# CanarySchematic3_0.net
KiCad netlist of a schematic drawn in EAGLE
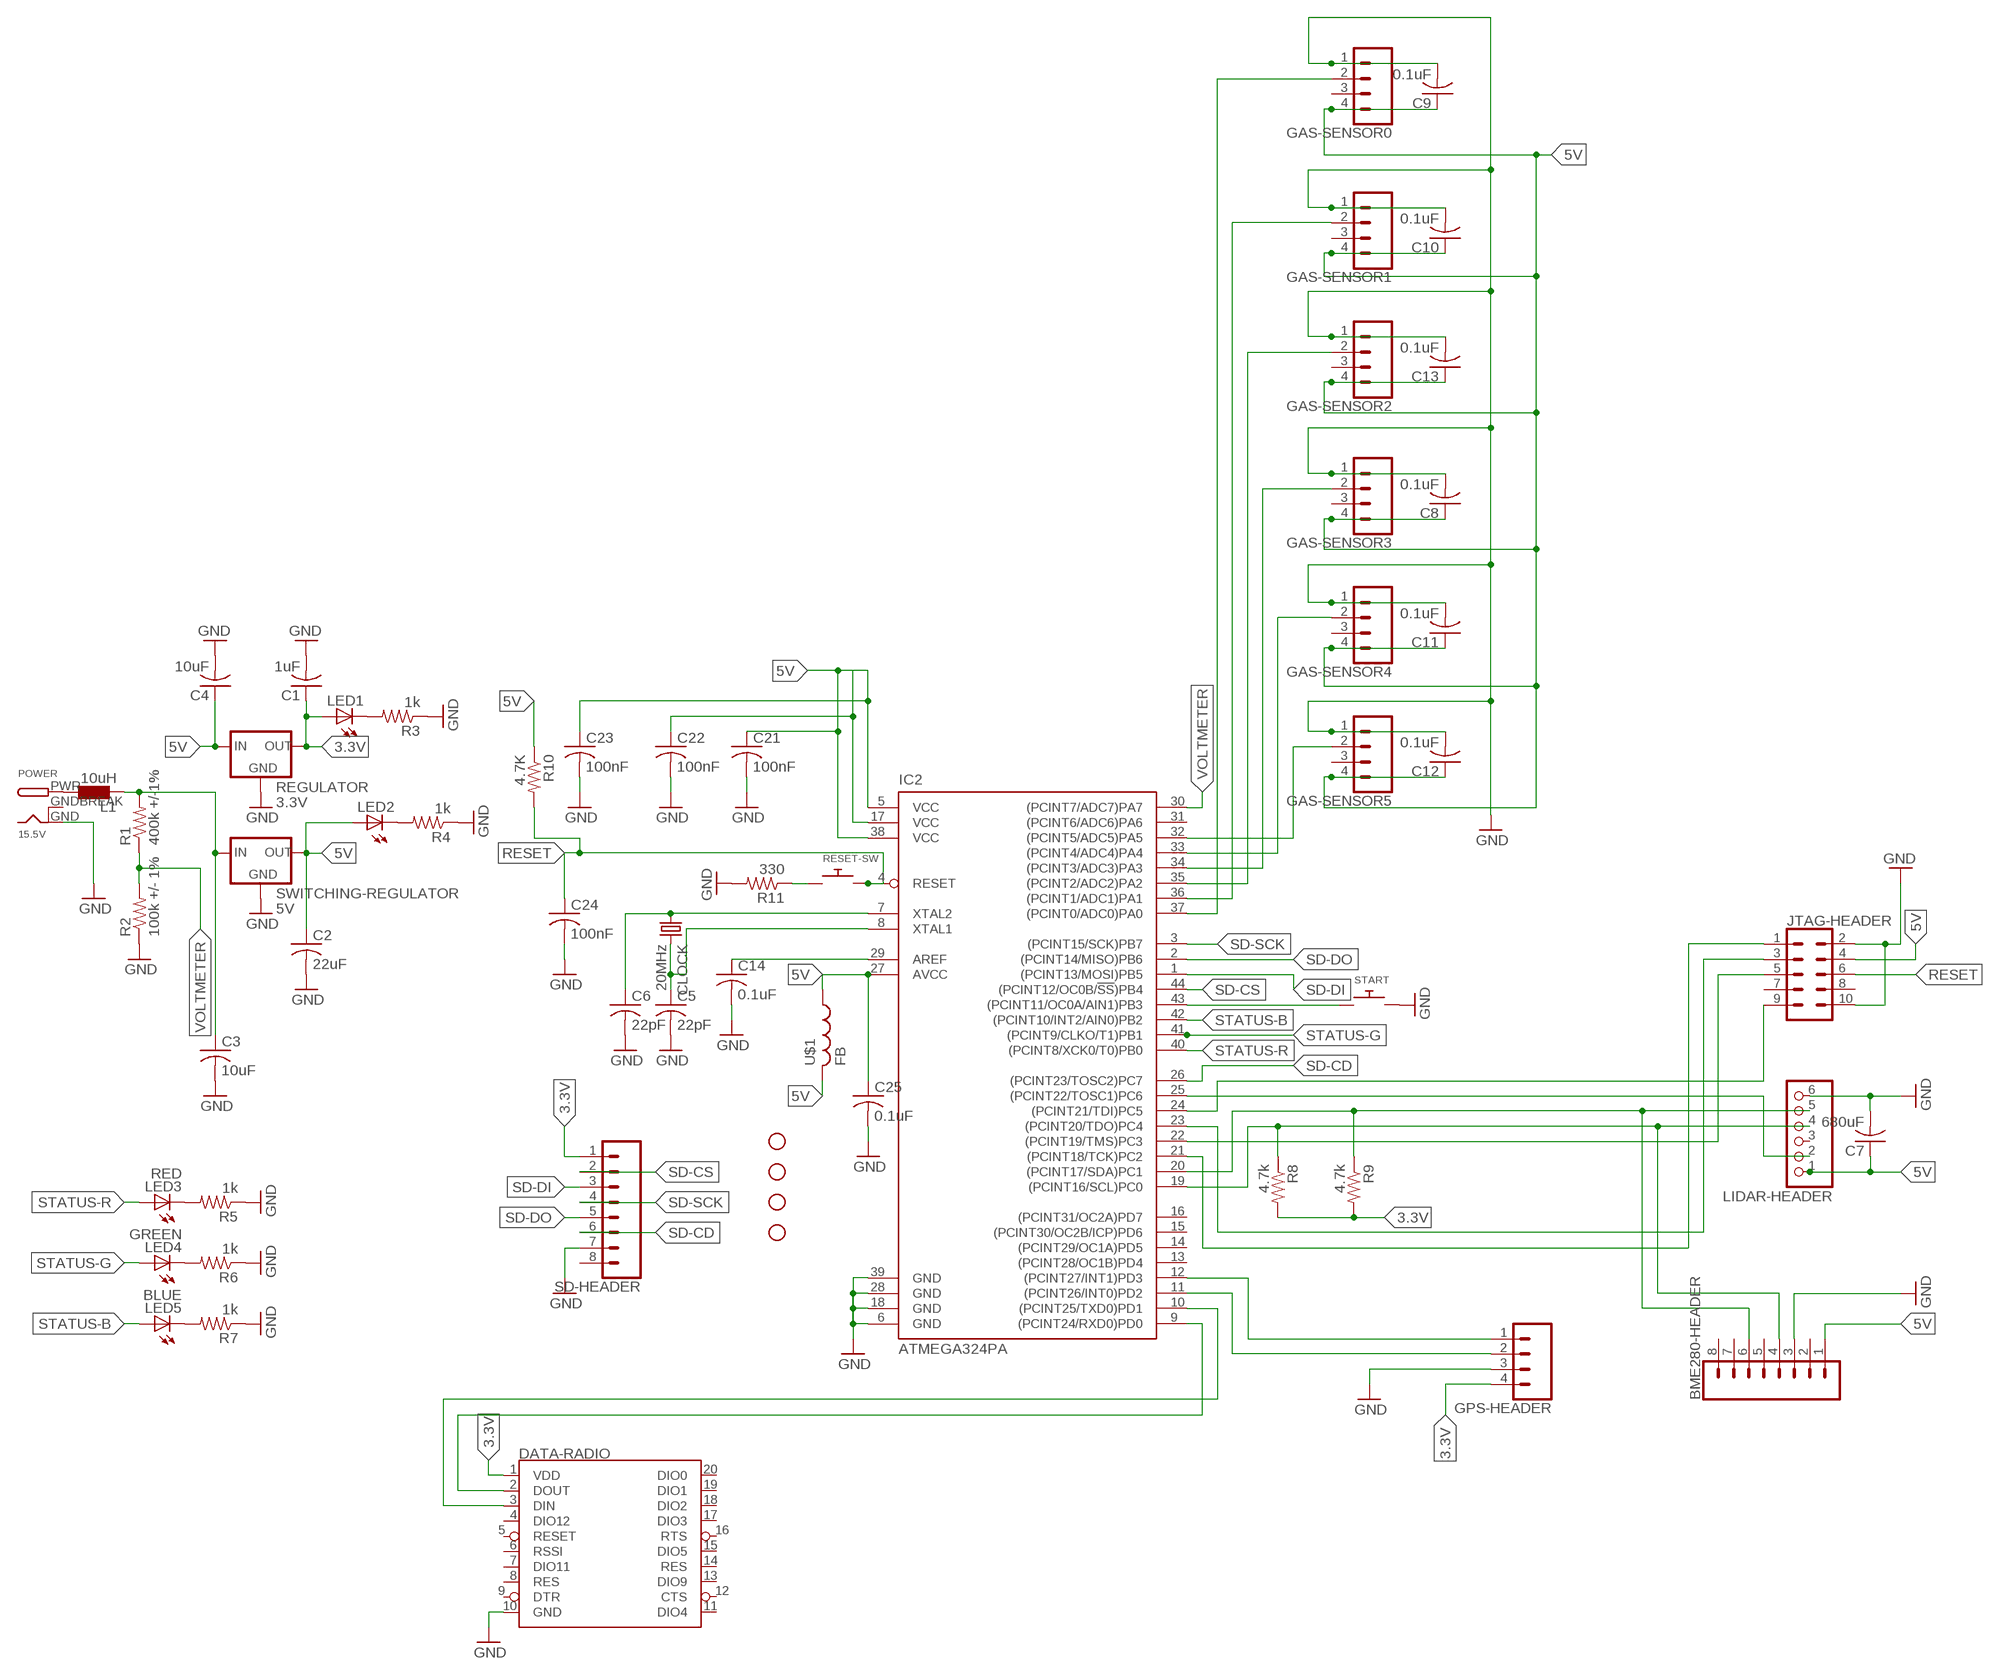
[diagram p0: schematic, sheet 1]

(export (version "E")
  (design (tool "Eeschema 10.0.6"))
  (components
    (comp (ref "BME280-HEADER")
      (value "CONN_08\"")
      (footprint "eagle-import:1X08")
      (libsource (lib "eagle-import") (part "CONN_08{dblquote}"))
    )
    (comp (ref "C1")
      (value "1uF")
      (footprint "eagle-import:C0805")
      (libsource (lib "eagle-import") (part "C-USC0805"))
    )
    (comp (ref "C2")
      (value "22uF")
      (footprint "eagle-import:C0805")
      (libsource (lib "eagle-import") (part "C-USC0805"))
    )
    (comp (ref "C3")
      (value "10uF")
      (footprint "eagle-import:C0805")
      (libsource (lib "eagle-import") (part "C-USC0805"))
    )
    (comp (ref "C4")
      (value "10uF")
      (footprint "eagle-import:C0805")
      (libsource (lib "eagle-import") (part "C-USC0805"))
    )
    (comp (ref "C5")
      (value "22pF")
      (footprint "eagle-import:C0805")
      (libsource (lib "eagle-import") (part "C-USC0805"))
    )
    (comp (ref "C6")
      (value "22pF")
      (footprint "eagle-import:C0805")
      (libsource (lib "eagle-import") (part "C-USC0805"))
    )
    (comp (ref "C7")
      (value "680uF")
      (footprint "eagle-import:C0805")
      (libsource (lib "eagle-import") (part "C-USC0805"))
    )
    (comp (ref "C8")
      (value "0.1uF")
      (footprint "eagle-import:C0805")
      (libsource (lib "eagle-import") (part "C-USC0805"))
    )
    (comp (ref "C9")
      (value "0.1uF")
      (footprint "eagle-import:C0805")
      (libsource (lib "eagle-import") (part "C-USC0805"))
    )
    (comp (ref "C10")
      (value "0.1uF")
      (footprint "eagle-import:C0805")
      (libsource (lib "eagle-import") (part "C-USC0805"))
    )
    (comp (ref "C11")
      (value "0.1uF")
      (footprint "eagle-import:C0805")
      (libsource (lib "eagle-import") (part "C-USC0805"))
    )
    (comp (ref "C12")
      (value "0.1uF")
      (footprint "eagle-import:C0603")
      (libsource (lib "eagle-import") (part "C-USC0603"))
    )
    (comp (ref "C13")
      (value "0.1uF")
      (footprint "eagle-import:C0805")
      (libsource (lib "eagle-import") (part "C-USC0805"))
    )
    (comp (ref "C14")
      (value "0.1uF")
      (footprint "eagle-import:C0805")
      (libsource (lib "eagle-import") (part "C-USC0805"))
    )
    (comp (ref "C21")
      (value "100nF")
      (footprint "eagle-import:C0805")
      (libsource (lib "eagle-import") (part "C-USC0805"))
    )
    (comp (ref "C22")
      (value "100nF")
      (footprint "eagle-import:C0805")
      (libsource (lib "eagle-import") (part "C-USC0805"))
    )
    (comp (ref "C23")
      (value "100nF")
      (footprint "eagle-import:C0805")
      (libsource (lib "eagle-import") (part "C-USC0805"))
    )
    (comp (ref "C24")
      (value "100nF")
      (footprint "eagle-import:C0805")
      (libsource (lib "eagle-import") (part "C-USC0805"))
    )
    (comp (ref "C25")
      (value "0.1uF")
      (footprint "eagle-import:C0805")
      (libsource (lib "eagle-import") (part "C-USC0805"))
    )
    (comp (ref "CLOCK")
      (value "20MHz")
      (footprint "eagle-import:86SMX")
      (libsource (lib "eagle-import") (part "CRYSTAL68SMX"))
    )
    (comp (ref "DATA-RADIO")
      (value "XBEE")
      (footprint "eagle-import:XBEE")
      (libsource (lib "eagle-import") (part "XBEE"))
    )
    (comp (ref "GAS-SENSOR0")
      (value "CONN_04")
      (footprint "eagle-import:1X04")
      (libsource (lib "eagle-import") (part "CONN_04"))
    )
    (comp (ref "GAS-SENSOR1")
      (value "CONN_04")
      (footprint "eagle-import:1X04")
      (libsource (lib "eagle-import") (part "CONN_04"))
    )
    (comp (ref "GAS-SENSOR2")
      (value "CONN_04")
      (footprint "eagle-import:1X04")
      (libsource (lib "eagle-import") (part "CONN_04"))
    )
    (comp (ref "GAS-SENSOR3")
      (value "CONN_04")
      (footprint "eagle-import:1X04")
      (libsource (lib "eagle-import") (part "CONN_04"))
    )
    (comp (ref "GAS-SENSOR4")
      (value "CONN_04")
      (footprint "eagle-import:1X04")
      (libsource (lib "eagle-import") (part "CONN_04"))
    )
    (comp (ref "GAS-SENSOR5")
      (value "CONN_04")
      (footprint "eagle-import:1X04")
      (libsource (lib "eagle-import") (part "CONN_04"))
    )
    (comp (ref "GPS-HEADER")
      (value "CONN_04")
      (footprint "eagle-import:1X04")
      (libsource (lib "eagle-import") (part "CONN_04"))
    )
    (comp (ref "H8")
      (value "STAND-OFF")
      (footprint "eagle-import:STAND-OFF")
      (libsource (lib "eagle-import") (part "STAND-OFF"))
    )
    (comp (ref "IC2")
      (value "ATMEGA324PA")
      (footprint "eagle-import:TQFP44")
      (fields (field (name "MPN") "ATMEGA644PV-10AU"))
      (libsource (lib "eagle-import") (part "ATMEGA644A"))
    )
    (comp (ref "JTAG-HEADER")
      (value "CONN_05X2PTH")
      (footprint "eagle-import:2X5")
      (libsource (lib "eagle-import") (part "CONN_05X2PTH"))
    )
    (comp (ref "L1")
      (value "10uH")
      (footprint "eagle-import:L1812")
      (libsource (lib "eagle-import") (part "L"))
    )
    (comp (ref "LED1")
      (value "LEDCHIP-LED0805")
      (footprint "eagle-import:CHIP-LED0805")
      (libsource (lib "eagle-import") (part "LEDCHIP-LED0805"))
    )
    (comp (ref "LED2")
      (value "LEDCHIP-LED0805")
      (footprint "eagle-import:CHIP-LED0805")
      (libsource (lib "eagle-import") (part "LEDCHIP-LED0805"))
    )
    (comp (ref "LED3")
      (value "RED")
      (footprint "eagle-import:CHIP-LED0805")
      (libsource (lib "eagle-import") (part "LEDCHIP-LED0805"))
    )
    (comp (ref "LED4")
      (value "GREEN")
      (footprint "eagle-import:CHIP-LED0805")
      (libsource (lib "eagle-import") (part "LEDCHIP-LED0805"))
    )
    (comp (ref "LED5")
      (value "BLUE")
      (footprint "eagle-import:CHIP-LED0805")
      (libsource (lib "eagle-import") (part "LEDCHIP-LED0805"))
    )
    (comp (ref "LIDAR-HEADER")
      (value "PINHD-1X6")
      (footprint "eagle-import:1X06")
      (libsource (lib "eagle-import") (part "PINHD-1X6"))
    )
    (comp (ref "MOUNT-HOLE1")
      (value "STAND-OFF")
      (footprint "eagle-import:STAND-OFF")
      (libsource (lib "eagle-import") (part "STAND-OFF"))
    )
    (comp (ref "MOUNT-HOLE2")
      (value "STAND-OFF")
      (footprint "eagle-import:STAND-OFF")
      (libsource (lib "eagle-import") (part "STAND-OFF"))
    )
    (comp (ref "MOUNT-HOLE3")
      (value "STAND-OFF")
      (footprint "eagle-import:STAND-OFF")
      (libsource (lib "eagle-import") (part "STAND-OFF"))
    )
    (comp (ref "POWER")
      (value "15.5V")
      (footprint "eagle-import:DCJACK_2MM_PTH")
      (libsource (lib "eagle-import") (part "DCBARRELPTH"))
    )
    (comp (ref "R1")
      (value "400k +/-1%")
      (footprint "eagle-import:M0805")
      (libsource (lib "eagle-import") (part "R-US_M0805"))
    )
    (comp (ref "R2")
      (value "100k +/- 1%")
      (footprint "eagle-import:M0805")
      (libsource (lib "eagle-import") (part "R-US_M0805"))
    )
    (comp (ref "R3")
      (value "1k")
      (footprint "eagle-import:M0805")
      (libsource (lib "eagle-import") (part "R-US_M0805"))
    )
    (comp (ref "R4")
      (value "1k")
      (footprint "eagle-import:M0805")
      (libsource (lib "eagle-import") (part "R-US_M0805"))
    )
    (comp (ref "R5")
      (value "1k")
      (footprint "eagle-import:M0805")
      (libsource (lib "eagle-import") (part "R-US_M0805"))
    )
    (comp (ref "R6")
      (value "1k")
      (footprint "eagle-import:M0805")
      (libsource (lib "eagle-import") (part "R-US_M0805"))
    )
    (comp (ref "R7")
      (value "1k")
      (footprint "eagle-import:M0805")
      (libsource (lib "eagle-import") (part "R-US_M0805"))
    )
    (comp (ref "R8")
      (value "4.7k")
      (footprint "eagle-import:M0805")
      (libsource (lib "eagle-import") (part "R-US_M0805"))
    )
    (comp (ref "R9")
      (value "4.7k")
      (footprint "eagle-import:M0805")
      (libsource (lib "eagle-import") (part "R-US_M0805"))
    )
    (comp (ref "R10")
      (value "4.7K")
      (footprint "eagle-import:M0805")
      (libsource (lib "eagle-import") (part "R-US_M0805"))
    )
    (comp (ref "R11")
      (value "330")
      (footprint "eagle-import:M0805")
      (libsource (lib "eagle-import") (part "R-US_M0805"))
    )
    (comp (ref "REGULATOR")
      (value "3.3V")
      (footprint "eagle-import:TO220-IGO")
      (libsource (lib "eagle-import") (part "V_REG_78XXSINK"))
    )
    (comp (ref "RESET-SW")
      (value "SWITCH_PUSHBUTTONSOFTTOUCHSMD_SJ")
      (footprint "eagle-import:PUSHBUTTON_SMD_SJ")
      (libsource (lib "eagle-import") (part "SWITCH_PUSHBUTTONSOFTTOUCHSMD_SJ"))
    )
    (comp (ref "SD-HEADER")
      (value "CONN_08\"")
      (footprint "eagle-import:1X08")
      (libsource (lib "eagle-import") (part "CONN_08{dblquote}"))
    )
    (comp (ref "START")
      (value "SWITCH_PUSHBUTTONSOFTTOUCHSMD_SJ")
      (footprint "eagle-import:PUSHBUTTON_SMD_SJ")
      (libsource (lib "eagle-import") (part "SWITCH_PUSHBUTTONSOFTTOUCHSMD_SJ"))
    )
    (comp (ref "SWITCHING-REGULATOR")
      (value "5V")
      (footprint "eagle-import:TO220-IGO")
      (libsource (lib "eagle-import") (part "V_REG_78XXSINK"))
    )
    (comp (ref "U$1") (value "FB") (footprint "eagle-import:FB") (libsource (lib "eagle-import") (part "FB")))
  )
  (nets
    (net (code "1") (name "/GNDBREAK") (class "Default")
      (node (ref "POWER") (pin "GNDBREAK") (pinfunction "GNDBREAK_GNDBREAK") (pintype "power_in"))
    )
    (net (code "2") (name "3.3V") (class "Default")
      (node (ref "C1") (pin "1") (pinfunction "1_1") (pintype "passive"))
      (node (ref "DATA-RADIO") (pin "1") (pinfunction "VDD_1") (pintype "power_in"))
      (node (ref "GPS-HEADER") (pin "4") (pinfunction "4_4") (pintype "passive"))
      (node (ref "LED1") (pin "A") (pinfunction "A_A") (pintype "passive"))
      (node (ref "R8") (pin "2") (pinfunction "2_2") (pintype "passive"))
      (node (ref "R9") (pin "2") (pinfunction "2_2") (pintype "passive"))
      (node (ref "REGULATOR") (pin "OUT") (pinfunction "OUT_OUT") (pintype "passive"))
      (node (ref "SD-HEADER") (pin "1") (pinfunction "1_1") (pintype "passive"))
    )
    (net (code "3") (name "5V") (class "Default")
      (node (ref "BME280-HEADER") (pin "1") (pinfunction "1_1") (pintype "passive"))
      (node (ref "C10") (pin "1") (pinfunction "1_1") (pintype "passive"))
      (node (ref "C11") (pin "1") (pinfunction "1_1") (pintype "passive"))
      (node (ref "C12") (pin "1") (pinfunction "1_1") (pintype "passive"))
      (node (ref "C13") (pin "1") (pinfunction "1_1") (pintype "passive"))
      (node (ref "C2") (pin "1") (pinfunction "1_1") (pintype "passive"))
      (node (ref "C21") (pin "1") (pinfunction "1_1") (pintype "passive"))
      (node (ref "C22") (pin "1") (pinfunction "1_1") (pintype "passive"))
      (node (ref "C23") (pin "1") (pinfunction "1_1") (pintype "passive"))
      (node (ref "C25") (pin "1") (pinfunction "1_1") (pintype "passive"))
      (node (ref "C4") (pin "1") (pinfunction "1_1") (pintype "passive"))
      (node (ref "C7") (pin "1") (pinfunction "1_1") (pintype "passive"))
      (node (ref "C8") (pin "1") (pinfunction "1_1") (pintype "passive"))
      (node (ref "C9") (pin "1") (pinfunction "1_1") (pintype "passive"))
      (node (ref "GAS-SENSOR0") (pin "4") (pinfunction "4_4") (pintype "passive"))
      (node (ref "GAS-SENSOR1") (pin "4") (pinfunction "4_4") (pintype "passive"))
      (node (ref "GAS-SENSOR2") (pin "4") (pinfunction "4_4") (pintype "passive"))
      (node (ref "GAS-SENSOR3") (pin "4") (pinfunction "4_4") (pintype "passive"))
      (node (ref "GAS-SENSOR4") (pin "4") (pinfunction "4_4") (pintype "passive"))
      (node (ref "GAS-SENSOR5") (pin "4") (pinfunction "4_4") (pintype "passive"))
      (node (ref "IC2") (pin "17") (pinfunction "VCC_17") (pintype "power_in"))
      (node (ref "IC2") (pin "27") (pinfunction "AVCC_27") (pintype "power_in"))
      (node (ref "IC2") (pin "38") (pinfunction "VCC_38") (pintype "power_in"))
      (node (ref "IC2") (pin "5") (pinfunction "VCC_5") (pintype "power_in"))
      (node (ref "JTAG-HEADER") (pin "4") (pinfunction "4_4") (pintype "passive"))
      (node (ref "LED2") (pin "A") (pinfunction "A_A") (pintype "passive"))
      (node (ref "LIDAR-HEADER") (pin "1") (pinfunction "1_1") (pintype "passive"))
      (node (ref "REGULATOR") (pin "IN") (pinfunction "IN_IN") (pintype "input"))
      (node (ref "SWITCHING-REGULATOR") (pin "OUT") (pinfunction "OUT_OUT") (pintype "passive"))
      (node (ref "U$1") (pin "P$1") (pinfunction "1_P$1") (pintype "passive"))
    )
    (net (code "4") (name "GND") (class "Default")
      (node (ref "BME280-HEADER") (pin "3") (pinfunction "3_3") (pintype "passive"))
      (node (ref "C1") (pin "2") (pinfunction "2_2") (pintype "passive"))
      (node (ref "C10") (pin "2") (pinfunction "2_2") (pintype "passive"))
      (node (ref "C11") (pin "2") (pinfunction "2_2") (pintype "passive"))
      (node (ref "C12") (pin "2") (pinfunction "2_2") (pintype "passive"))
      (node (ref "C13") (pin "2") (pinfunction "2_2") (pintype "passive"))
      (node (ref "C14") (pin "2") (pinfunction "2_2") (pintype "passive"))
      (node (ref "C2") (pin "2") (pinfunction "2_2") (pintype "passive"))
      (node (ref "C21") (pin "2") (pinfunction "2_2") (pintype "passive"))
      (node (ref "C22") (pin "2") (pinfunction "2_2") (pintype "passive"))
      (node (ref "C23") (pin "2") (pinfunction "2_2") (pintype "passive"))
      (node (ref "C24") (pin "2") (pinfunction "2_2") (pintype "passive"))
      (node (ref "C25") (pin "2") (pinfunction "2_2") (pintype "passive"))
      (node (ref "C3") (pin "2") (pinfunction "2_2") (pintype "passive"))
      (node (ref "C4") (pin "2") (pinfunction "2_2") (pintype "passive"))
      (node (ref "C5") (pin "2") (pinfunction "2_2") (pintype "passive"))
      (node (ref "C6") (pin "2") (pinfunction "2_2") (pintype "passive"))
      (node (ref "C7") (pin "2") (pinfunction "2_2") (pintype "passive"))
      (node (ref "C8") (pin "2") (pinfunction "2_2") (pintype "passive"))
      (node (ref "C9") (pin "2") (pinfunction "2_2") (pintype "passive"))
      (node (ref "DATA-RADIO") (pin "10") (pinfunction "GND_10") (pintype "power_in"))
      (node (ref "GAS-SENSOR0") (pin "1") (pinfunction "1_1") (pintype "passive"))
      (node (ref "GAS-SENSOR1") (pin "1") (pinfunction "1_1") (pintype "passive"))
      (node (ref "GAS-SENSOR2") (pin "1") (pinfunction "1_1") (pintype "passive"))
      (node (ref "GAS-SENSOR3") (pin "1") (pinfunction "1_1") (pintype "passive"))
      (node (ref "GAS-SENSOR4") (pin "1") (pinfunction "1_1") (pintype "passive"))
      (node (ref "GAS-SENSOR5") (pin "1") (pinfunction "1_1") (pintype "passive"))
      (node (ref "GPS-HEADER") (pin "3") (pinfunction "3_3") (pintype "passive"))
      (node (ref "IC2") (pin "18") (pinfunction "GND_18") (pintype "power_in"))
      (node (ref "IC2") (pin "28") (pinfunction "GND_28") (pintype "power_in"))
      (node (ref "IC2") (pin "39") (pinfunction "GND_39") (pintype "power_in"))
      (node (ref "IC2") (pin "6") (pinfunction "GND_6") (pintype "power_in"))
      (node (ref "JTAG-HEADER") (pin "10") (pinfunction "10_10") (pintype "passive"))
      (node (ref "JTAG-HEADER") (pin "2") (pinfunction "2_2") (pintype "passive"))
      (node (ref "LIDAR-HEADER") (pin "6") (pinfunction "6_6") (pintype "passive"))
      (node (ref "POWER") (pin "GND") (pinfunction "GND_GND") (pintype "power_in"))
      (node (ref "R11") (pin "2") (pinfunction "2_2") (pintype "passive"))
      (node (ref "R2") (pin "1") (pinfunction "1_1") (pintype "passive"))
      (node (ref "R3") (pin "1") (pinfunction "1_1") (pintype "passive"))
      (node (ref "R4") (pin "1") (pinfunction "1_1") (pintype "passive"))
      (node (ref "R5") (pin "1") (pinfunction "1_1") (pintype "passive"))
      (node (ref "R6") (pin "1") (pinfunction "1_1") (pintype "passive"))
      (node (ref "R7") (pin "1") (pinfunction "1_1") (pintype "passive"))
      (node (ref "REGULATOR") (pin "GND") (pinfunction "GND_GND") (pintype "input"))
      (node (ref "SD-HEADER") (pin "7") (pinfunction "7_7") (pintype "passive"))
      (node (ref "START") (pin "P$2") (pinfunction "P$2_P$2") (pintype "passive"))
      (node (ref "SWITCHING-REGULATOR") (pin "GND") (pinfunction "GND_GND") (pintype "input"))
    )
    (net (code "5") (name "Net-(C3-Pad1)") (class "Default")
      (node (ref "C3") (pin "1") (pinfunction "1_1") (pintype "passive"))
      (node (ref "L1") (pin "2") (pinfunction "2_2") (pintype "passive"))
      (node (ref "R1") (pin "2") (pinfunction "2_2") (pintype "passive"))
      (node (ref "SWITCHING-REGULATOR") (pin "IN") (pinfunction "IN_IN") (pintype "input"))
    )
    (net (code "6") (name "Net-(CLOCK-2)") (class "Default")
      (node (ref "C5") (pin "1") (pinfunction "1_1") (pintype "passive"))
      (node (ref "CLOCK") (pin "4") (pinfunction "2_4") (pintype "passive"))
      (node (ref "IC2") (pin "8") (pinfunction "XTAL1_8") (pintype "bidirectional"))
    )
    (net (code "7") (name "Net-(DATA-RADIO-DIN)") (class "Default")
      (node (ref "DATA-RADIO") (pin "3") (pinfunction "DIN_3") (pintype "input"))
      (node (ref "IC2") (pin "10") (pinfunction "(PCINT25/TXD0)PD1_10") (pintype "bidirectional"))
    )
    (net (code "8") (name "Net-(DATA-RADIO-DOUT)") (class "Default")
      (node (ref "DATA-RADIO") (pin "2") (pinfunction "DOUT_2") (pintype "output"))
      (node (ref "IC2") (pin "9") (pinfunction "(PCINT24/RXD0)PD0_9") (pintype "bidirectional"))
    )
    (net (code "9") (name "Net-(IC2-(PCINT0{slash}ADC0)PA0)") (class "Default")
      (node (ref "GAS-SENSOR0") (pin "2") (pinfunction "2_2") (pintype "passive"))
      (node (ref "IC2") (pin "37") (pinfunction "(PCINT0/ADC0)PA0_37") (pintype "bidirectional"))
    )
    (net (code "10") (name "Net-(IC2-(PCINT1{slash}ADC1)PA1)") (class "Default")
      (node (ref "GAS-SENSOR1") (pin "2") (pinfunction "2_2") (pintype "passive"))
      (node (ref "IC2") (pin "36") (pinfunction "(PCINT1/ADC1)PA1_36") (pintype "bidirectional"))
    )
    (net (code "11") (name "Net-(IC2-(PCINT2{slash}ADC2)PA2)") (class "Default")
      (node (ref "GAS-SENSOR2") (pin "2") (pinfunction "2_2") (pintype "passive"))
      (node (ref "IC2") (pin "35") (pinfunction "(PCINT2/ADC2)PA2_35") (pintype "bidirectional"))
    )
    (net (code "12") (name "Net-(IC2-(PCINT3{slash}ADC3)PA3)") (class "Default")
      (node (ref "GAS-SENSOR3") (pin "2") (pinfunction "2_2") (pintype "passive"))
      (node (ref "IC2") (pin "34") (pinfunction "(PCINT3/ADC3)PA3_34") (pintype "bidirectional"))
    )
    (net (code "13") (name "Net-(IC2-(PCINT4{slash}ADC4)PA4)") (class "Default")
      (node (ref "GAS-SENSOR4") (pin "2") (pinfunction "2_2") (pintype "passive"))
      (node (ref "IC2") (pin "33") (pinfunction "(PCINT4/ADC4)PA4_33") (pintype "bidirectional"))
    )
    (net (code "14") (name "Net-(IC2-(PCINT5{slash}ADC5)PA5)") (class "Default")
      (node (ref "GAS-SENSOR5") (pin "2") (pinfunction "2_2") (pintype "passive"))
      (node (ref "IC2") (pin "32") (pinfunction "(PCINT5/ADC5)PA5_32") (pintype "bidirectional"))
    )
    (net (code "15") (name "Net-(IC2-(PCINT11{slash}OC0A{slash}AIN1)PB3)") (class "Default")
      (node (ref "IC2") (pin "43") (pinfunction "(PCINT11/OC0A/AIN1)PB3_43") (pintype "bidirectional"))
      (node (ref "START") (pin "P$1") (pinfunction "P$1_P$1") (pintype "passive"))
    )
    (net (code "16") (name "Net-(IC2-(PCINT16{slash}SCL)PC0)") (class "Default")
      (node (ref "BME280-HEADER") (pin "4") (pinfunction "4_4") (pintype "passive"))
      (node (ref "IC2") (pin "19") (pinfunction "(PCINT16/SCL)PC0_19") (pintype "output"))
      (node (ref "LIDAR-HEADER") (pin "4") (pinfunction "4_4") (pintype "passive"))
      (node (ref "R8") (pin "1") (pinfunction "1_1") (pintype "passive"))
    )
    (net (code "17") (name "Net-(IC2-(PCINT17{slash}SDA)PC1)") (class "Default")
      (node (ref "BME280-HEADER") (pin "6") (pinfunction "6_6") (pintype "passive"))
      (node (ref "IC2") (pin "20") (pinfunction "(PCINT17/SDA)PC1_20") (pintype "output"))
      (node (ref "LIDAR-HEADER") (pin "5") (pinfunction "5_5") (pintype "passive"))
      (node (ref "R9") (pin "1") (pinfunction "1_1") (pintype "passive"))
    )
    (net (code "18") (name "Net-(IC2-(PCINT18{slash}TCK)PC2)") (class "Default")
      (node (ref "IC2") (pin "21") (pinfunction "(PCINT18/TCK)PC2_21") (pintype "output"))
      (node (ref "JTAG-HEADER") (pin "1") (pinfunction "1_1") (pintype "passive"))
    )
    (net (code "19") (name "Net-(IC2-(PCINT19{slash}TMS)PC3)") (class "Default")
      (node (ref "IC2") (pin "22") (pinfunction "(PCINT19/TMS)PC3_22") (pintype "output"))
      (node (ref "JTAG-HEADER") (pin "5") (pinfunction "5_5") (pintype "passive"))
    )
    (net (code "20") (name "Net-(IC2-(PCINT20{slash}TDO)PC4)") (class "Default")
      (node (ref "IC2") (pin "23") (pinfunction "(PCINT20/TDO)PC4_23") (pintype "output"))
      (node (ref "JTAG-HEADER") (pin "3") (pinfunction "3_3") (pintype "passive"))
    )
    (net (code "21") (name "Net-(IC2-(PCINT21{slash}TDI)PC5)") (class "Default")
      (node (ref "IC2") (pin "24") (pinfunction "(PCINT21/TDI)PC5_24") (pintype "output"))
      (node (ref "JTAG-HEADER") (pin "9") (pinfunction "9_9") (pintype "passive"))
    )
    (net (code "22") (name "Net-(IC2-(PCINT22{slash}TOSC1)PC6)") (class "Default")
      (node (ref "IC2") (pin "25") (pinfunction "(PCINT22/TOSC1)PC6_25") (pintype "output"))
      (node (ref "LIDAR-HEADER") (pin "2") (pinfunction "2_2") (pintype "passive"))
    )
    (net (code "23") (name "Net-(IC2-(PCINT26{slash}INT0)PD2)") (class "Default")
      (node (ref "GPS-HEADER") (pin "2") (pinfunction "2_2") (pintype "passive"))
      (node (ref "IC2") (pin "11") (pinfunction "(PCINT26/INT0)PD2_11") (pintype "bidirectional"))
    )
    (net (code "24") (name "Net-(IC2-(PCINT27{slash}INT1)PD3)") (class "Default")
      (node (ref "GPS-HEADER") (pin "1") (pinfunction "1_1") (pintype "passive"))
      (node (ref "IC2") (pin "12") (pinfunction "(PCINT27/INT1)PD3_12") (pintype "bidirectional"))
    )
    (net (code "25") (name "Net-(IC2-AREF)") (class "Default")
      (node (ref "C14") (pin "1") (pinfunction "1_1") (pintype "passive"))
      (node (ref "IC2") (pin "29") (pinfunction "AREF_29") (pintype "passive"))
    )
    (net (code "26") (name "Net-(IC2-XTAL2)") (class "Default")
      (node (ref "C6") (pin "1") (pinfunction "1_1") (pintype "passive"))
      (node (ref "CLOCK") (pin "1") (pinfunction "1_1") (pintype "passive"))
      (node (ref "IC2") (pin "7") (pinfunction "XTAL2_7") (pintype "bidirectional"))
    )
    (net (code "27") (name "Net-(L1-Pad1)") (class "Default")
      (node (ref "L1") (pin "1") (pinfunction "1_1") (pintype "passive"))
      (node (ref "POWER") (pin "PWR") (pinfunction "PWR_PWR") (pintype "power_in"))
    )
    (net (code "28") (name "Net-(LED1-PadC)") (class "Default")
      (node (ref "LED1") (pin "C") (pinfunction "C_C") (pintype "passive"))
      (node (ref "R3") (pin "2") (pinfunction "2_2") (pintype "passive"))
    )
    (net (code "29") (name "Net-(LED2-PadC)") (class "Default")
      (node (ref "LED2") (pin "C") (pinfunction "C_C") (pintype "passive"))
      (node (ref "R4") (pin "2") (pinfunction "2_2") (pintype "passive"))
    )
    (net (code "30") (name "Net-(LED3-PadC)") (class "Default")
      (node (ref "LED3") (pin "C") (pinfunction "C_C") (pintype "passive"))
      (node (ref "R5") (pin "2") (pinfunction "2_2") (pintype "passive"))
    )
    (net (code "31") (name "Net-(LED4-PadC)") (class "Default")
      (node (ref "LED4") (pin "C") (pinfunction "C_C") (pintype "passive"))
      (node (ref "R6") (pin "2") (pinfunction "2_2") (pintype "passive"))
    )
    (net (code "32") (name "Net-(LED5-PadC)") (class "Default")
      (node (ref "LED5") (pin "C") (pinfunction "C_C") (pintype "passive"))
      (node (ref "R7") (pin "2") (pinfunction "2_2") (pintype "passive"))
    )
    (net (code "33") (name "Net-(R11-Pad1)") (class "Default")
      (node (ref "R11") (pin "1") (pinfunction "1_1") (pintype "passive"))
      (node (ref "RESET-SW") (pin "P$1") (pinfunction "P$1_P$1") (pintype "passive"))
    )
    (net (code "34") (name "RESET") (class "Default")
      (node (ref "C24") (pin "1") (pinfunction "1_1") (pintype "passive"))
      (node (ref "IC2") (pin "4") (pinfunction "RESET_4") (pintype "input"))
      (node (ref "JTAG-HEADER") (pin "6") (pinfunction "6_6") (pintype "passive"))
      (node (ref "R10") (pin "2") (pinfunction "2_2") (pintype "passive"))
      (node (ref "RESET-SW") (pin "P$2") (pinfunction "P$2_P$2") (pintype "passive"))
    )
    (net (code "35") (name "SD-CD") (class "Default")
      (node (ref "IC2") (pin "26") (pinfunction "(PCINT23/TOSC2)PC7_26") (pintype "output"))
      (node (ref "SD-HEADER") (pin "6") (pinfunction "6_6") (pintype "passive"))
    )
    (net (code "36") (name "SD-CS") (class "Default")
      (node (ref "IC2") (pin "44") (pinfunction "(PCINT12/OC0B/~{SS})PB4_44") (pintype "bidirectional"))
      (node (ref "SD-HEADER") (pin "2") (pinfunction "2_2") (pintype "passive"))
    )
    (net (code "37") (name "SD-DI") (class "Default")
      (node (ref "IC2") (pin "1") (pinfunction "(PCINT13/MOSI)PB5_1") (pintype "bidirectional"))
      (node (ref "SD-HEADER") (pin "3") (pinfunction "3_3") (pintype "passive"))
    )
    (net (code "38") (name "SD-DO") (class "Default")
      (node (ref "IC2") (pin "2") (pinfunction "(PCINT14/MISO)PB6_2") (pintype "bidirectional"))
      (node (ref "SD-HEADER") (pin "5") (pinfunction "5_5") (pintype "passive"))
    )
    (net (code "39") (name "SD-SCK") (class "Default")
      (node (ref "IC2") (pin "3") (pinfunction "(PCINT15/SCK)PB7_3") (pintype "bidirectional"))
      (node (ref "SD-HEADER") (pin "4") (pinfunction "4_4") (pintype "passive"))
    )
    (net (code "40") (name "STATUS-B") (class "Default")
      (node (ref "IC2") (pin "42") (pinfunction "(PCINT10/INT2/AIN0)PB2_42") (pintype "bidirectional"))
      (node (ref "LED5") (pin "A") (pinfunction "A_A") (pintype "passive"))
    )
    (net (code "41") (name "STATUS-G") (class "Default")
      (node (ref "IC2") (pin "41") (pinfunction "(PCINT9/CLKO/T1)PB1_41") (pintype "bidirectional"))
      (node (ref "LED4") (pin "A") (pinfunction "A_A") (pintype "passive"))
    )
    (net (code "42") (name "STATUS-R") (class "Default")
      (node (ref "IC2") (pin "40") (pinfunction "(PCINT8/XCK0/T0)PB0_40") (pintype "bidirectional"))
      (node (ref "LED3") (pin "A") (pinfunction "A_A") (pintype "passive"))
    )
    (net (code "43") (name "VOLTMETER") (class "Default")
      (node (ref "IC2") (pin "30") (pinfunction "(PCINT7/ADC7)PA7_30") (pintype "bidirectional"))
      (node (ref "R1") (pin "1") (pinfunction "1_1") (pintype "passive"))
      (node (ref "R2") (pin "2") (pinfunction "2_2") (pintype "passive"))
    )
    (net (code "44") (name "unconnected-(BME280-HEADER-Pad2)") (class "Default")
      (node (ref "BME280-HEADER") (pin "2") (pinfunction "2_2") (pintype "passive"))
    )
    (net (code "45") (name "unconnected-(BME280-HEADER-Pad5)") (class "Default")
      (node (ref "BME280-HEADER") (pin "5") (pinfunction "5_5") (pintype "passive"))
    )
    (net (code "46") (name "unconnected-(BME280-HEADER-Pad7)") (class "Default")
      (node (ref "BME280-HEADER") (pin "7") (pinfunction "7_7") (pintype "passive"))
    )
    (net (code "47") (name "unconnected-(BME280-HEADER-Pad8)") (class "Default")
      (node (ref "BME280-HEADER") (pin "8") (pinfunction "8_8") (pintype "passive"))
    )
    (net (code "48") (name "unconnected-(DATA-RADIO-CTS-Pad12)") (class "Default")
      (node (ref "DATA-RADIO") (pin "12") (pinfunction "CTS_12") (pintype "output"))
    )
    (net (code "49") (name "unconnected-(DATA-RADIO-DIO0-Pad20)") (class "Default")
      (node (ref "DATA-RADIO") (pin "20") (pinfunction "DIO0_20") (pintype "bidirectional"))
    )
    (net (code "50") (name "unconnected-(DATA-RADIO-DIO1-Pad19)") (class "Default")
      (node (ref "DATA-RADIO") (pin "19") (pinfunction "DIO1_19") (pintype "bidirectional"))
    )
    (net (code "51") (name "unconnected-(DATA-RADIO-DIO2-Pad18)") (class "Default")
      (node (ref "DATA-RADIO") (pin "18") (pinfunction "DIO2_18") (pintype "bidirectional"))
    )
    (net (code "52") (name "unconnected-(DATA-RADIO-DIO3-Pad17)") (class "Default")
      (node (ref "DATA-RADIO") (pin "17") (pinfunction "DIO3_17") (pintype "bidirectional"))
    )
    (net (code "53") (name "unconnected-(DATA-RADIO-DIO4-Pad11)") (class "Default")
      (node (ref "DATA-RADIO") (pin "11") (pinfunction "DIO4_11") (pintype "bidirectional"))
    )
    (net (code "54") (name "unconnected-(DATA-RADIO-DIO5-Pad15)") (class "Default")
      (node (ref "DATA-RADIO") (pin "15") (pinfunction "DIO5_15") (pintype "bidirectional"))
    )
    (net (code "55") (name "unconnected-(DATA-RADIO-DIO9-Pad13)") (class "Default")
      (node (ref "DATA-RADIO") (pin "13") (pinfunction "DIO9_13") (pintype "bidirectional"))
    )
    (net (code "56") (name "unconnected-(DATA-RADIO-DIO11-Pad7)") (class "Default")
      (node (ref "DATA-RADIO") (pin "7") (pinfunction "DIO11_7") (pintype "bidirectional"))
    )
    (net (code "57") (name "unconnected-(DATA-RADIO-DIO12-Pad4)") (class "Default")
      (node (ref "DATA-RADIO") (pin "4") (pinfunction "DIO12_4") (pintype "bidirectional"))
    )
    (net (code "58") (name "unconnected-(DATA-RADIO-DTR-Pad9)") (class "Default")
      (node (ref "DATA-RADIO") (pin "9") (pinfunction "DTR_9") (pintype "bidirectional"))
    )
    (net (code "59") (name "unconnected-(DATA-RADIO-RES-Pad8)") (class "Default")
      (node (ref "DATA-RADIO") (pin "8") (pinfunction "RES_8") (pintype "bidirectional"))
    )
    (net (code "60") (name "unconnected-(DATA-RADIO-RES-Pad14)") (class "Default")
      (node (ref "DATA-RADIO") (pin "14") (pinfunction "RES_14") (pintype "bidirectional"))
    )
    (net (code "61") (name "unconnected-(DATA-RADIO-RESET-Pad5)") (class "Default")
      (node (ref "DATA-RADIO") (pin "5") (pinfunction "RESET_5") (pintype "input"))
    )
    (net (code "62") (name "unconnected-(DATA-RADIO-RSSI-Pad6)") (class "Default")
      (node (ref "DATA-RADIO") (pin "6") (pinfunction "RSSI_6") (pintype "bidirectional"))
    )
    (net (code "63") (name "unconnected-(DATA-RADIO-RTS-Pad16)") (class "Default")
      (node (ref "DATA-RADIO") (pin "16") (pinfunction "RTS_16") (pintype "input"))
    )
    (net (code "64") (name "unconnected-(GAS-SENSOR0-Pad3)") (class "Default")
      (node (ref "GAS-SENSOR0") (pin "3") (pinfunction "3_3") (pintype "passive"))
    )
    (net (code "65") (name "unconnected-(GAS-SENSOR1-Pad3)") (class "Default")
      (node (ref "GAS-SENSOR1") (pin "3") (pinfunction "3_3") (pintype "passive"))
    )
    (net (code "66") (name "unconnected-(GAS-SENSOR2-Pad3)") (class "Default")
      (node (ref "GAS-SENSOR2") (pin "3") (pinfunction "3_3") (pintype "passive"))
    )
    (net (code "67") (name "unconnected-(GAS-SENSOR3-Pad3)") (class "Default")
      (node (ref "GAS-SENSOR3") (pin "3") (pinfunction "3_3") (pintype "passive"))
    )
    (net (code "68") (name "unconnected-(GAS-SENSOR4-Pad3)") (class "Default")
      (node (ref "GAS-SENSOR4") (pin "3") (pinfunction "3_3") (pintype "passive"))
    )
    (net (code "69") (name "unconnected-(GAS-SENSOR5-Pad3)") (class "Default")
      (node (ref "GAS-SENSOR5") (pin "3") (pinfunction "3_3") (pintype "passive"))
    )
    (net (code "70") (name "unconnected-(IC2-(PCINT6{slash}ADC6)PA6-Pad31)") (class "Default")
      (node (ref "IC2") (pin "31") (pinfunction "(PCINT6/ADC6)PA6_31") (pintype "bidirectional"))
    )
    (net (code "71") (name "unconnected-(IC2-(PCINT28{slash}OC1B)PD4-Pad13)") (class "Default")
      (node (ref "IC2") (pin "13") (pinfunction "(PCINT28/OC1B)PD4_13") (pintype "bidirectional"))
    )
    (net (code "72") (name "unconnected-(IC2-(PCINT29{slash}OC1A)PD5-Pad14)") (class "Default")
      (node (ref "IC2") (pin "14") (pinfunction "(PCINT29/OC1A)PD5_14") (pintype "bidirectional"))
    )
    (net (code "73") (name "unconnected-(IC2-(PCINT30{slash}OC2B{slash}ICP)PD6-Pad15)") (class "Default")
      (node (ref "IC2") (pin "15") (pinfunction "(PCINT30/OC2B/ICP)PD6_15") (pintype "bidirectional"))
    )
    (net (code "74") (name "unconnected-(IC2-(PCINT31{slash}OC2A)PD7-Pad16)") (class "Default")
      (node (ref "IC2") (pin "16") (pinfunction "(PCINT31/OC2A)PD7_16") (pintype "bidirectional"))
    )
    (net (code "75") (name "unconnected-(JTAG-HEADER-Pad7)") (class "Default")
      (node (ref "JTAG-HEADER") (pin "7") (pinfunction "7_7") (pintype "passive"))
    )
    (net (code "76") (name "unconnected-(JTAG-HEADER-Pad8)") (class "Default")
      (node (ref "JTAG-HEADER") (pin "8") (pinfunction "8_8") (pintype "passive"))
    )
    (net (code "77") (name "unconnected-(LIDAR-HEADER-Pad3)") (class "Default")
      (node (ref "LIDAR-HEADER") (pin "3") (pinfunction "3_3") (pintype "passive"))
    )
    (net (code "78") (name "unconnected-(R10-Pad1)") (class "Default")
      (node (ref "R10") (pin "1") (pinfunction "1_1") (pintype "passive"))
    )
    (net (code "79") (name "unconnected-(SD-HEADER-Pad8)") (class "Default")
      (node (ref "SD-HEADER") (pin "8") (pinfunction "8_8") (pintype "passive"))
    )
    (net (code "80") (name "unconnected-(U$1-2-PadP$2)") (class "Default")
      (node (ref "U$1") (pin "P$2") (pinfunction "2_P$2") (pintype "passive"))
    )
  )
)
